# gan_buck.net
KiCad netlist of a schematic drawn in Altium Designer
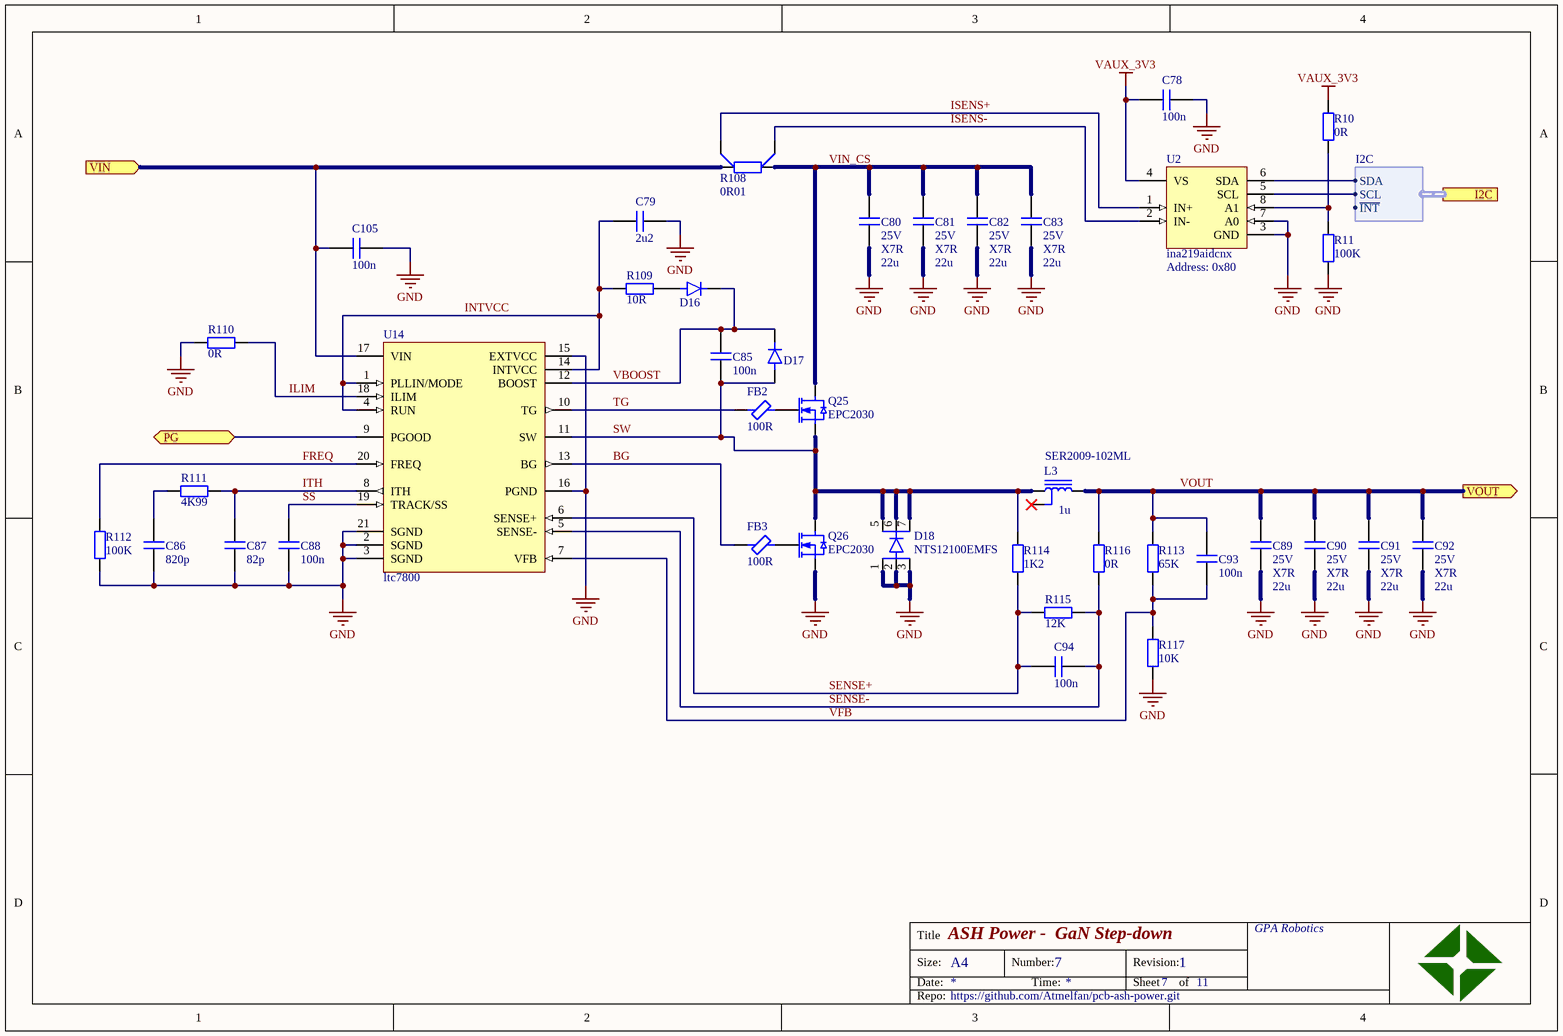
[diagram p0: gan_buck.SchDoc]

(export (version "E")
  (design (tool "Eeschema 10.0.6"))
  (components
    (comp (ref "C78")
      (value "100n")
      (footprint "CAPC1005X06N")
      (description "Capacitor")
      (fields (field (name "Comment") "cap"))
      (libsource (lib "lib_passives") (part "cap"))
    )
    (comp (ref "C79")
      (value "2u2")
      (footprint "CAPC2012X11N")
      (description "Capacitor")
      (fields (field (name "Comment") "cap"))
      (libsource (lib "lib_passives") (part "cap"))
    )
    (comp (ref "C80")
      (value "22u")
      (footprint "CAPC3225X14N")
      (description "Capacitor")
      (fields (field (name "VOLTAGE") "25V") (field (name "TYPE") "X7R") (field (name "Comment") "cap"))
      (libsource (lib "lib_passives") (part "cap"))
    )
    (comp (ref "C81")
      (value "22u")
      (footprint "CAPC3225X14N")
      (description "Capacitor")
      (fields (field (name "VOLTAGE") "25V") (field (name "TYPE") "X7R") (field (name "Comment") "cap"))
      (libsource (lib "lib_passives") (part "cap"))
    )
    (comp (ref "C82")
      (value "22u")
      (footprint "CAPC3225X14N")
      (description "Capacitor")
      (fields (field (name "VOLTAGE") "25V") (field (name "TYPE") "X7R") (field (name "Comment") "cap"))
      (libsource (lib "lib_passives") (part "cap"))
    )
    (comp (ref "C83")
      (value "22u")
      (footprint "CAPC3225X14N")
      (description "Capacitor")
      (fields (field (name "VOLTAGE") "25V") (field (name "TYPE") "X7R") (field (name "Comment") "cap"))
      (libsource (lib "lib_passives") (part "cap"))
    )
    (comp (ref "C85")
      (value "100n")
      (footprint "CAPC1608X08N")
      (description "Capacitor")
      (fields (field (name "Comment") "cap"))
      (libsource (lib "lib_passives") (part "cap"))
    )
    (comp (ref "C86")
      (value "820p")
      (footprint "CAPC1005X06N")
      (description "Capacitor")
      (fields (field (name "Comment") "cap"))
      (libsource (lib "lib_passives") (part "cap"))
    )
    (comp (ref "C87")
      (value "82p")
      (footprint "CAPC1005X06N")
      (description "Capacitor")
      (fields (field (name "Comment") "cap"))
      (libsource (lib "lib_passives") (part "cap"))
    )
    (comp (ref "C88")
      (value "100n")
      (footprint "CAPC1005X06N")
      (description "Capacitor")
      (fields (field (name "Comment") "cap"))
      (libsource (lib "lib_passives") (part "cap"))
    )
    (comp (ref "C89")
      (value "22u")
      (footprint "CAPC3225X14N")
      (description "Capacitor")
      (fields (field (name "VOLTAGE") "25V") (field (name "TYPE") "X7R") (field (name "Comment") "cap"))
      (libsource (lib "lib_passives") (part "cap"))
    )
    (comp (ref "C90")
      (value "22u")
      (footprint "CAPC3225X14N")
      (description "Capacitor")
      (fields (field (name "VOLTAGE") "25V") (field (name "TYPE") "X7R") (field (name "Comment") "cap"))
      (libsource (lib "lib_passives") (part "cap"))
    )
    (comp (ref "C91")
      (value "22u")
      (footprint "CAPC3225X14N")
      (description "Capacitor")
      (fields (field (name "VOLTAGE") "25V") (field (name "TYPE") "X7R") (field (name "Comment") "cap"))
      (libsource (lib "lib_passives") (part "cap"))
    )
    (comp (ref "C92")
      (value "22u")
      (footprint "CAPC3225X14N")
      (description "Capacitor")
      (fields (field (name "VOLTAGE") "25V") (field (name "TYPE") "X7R") (field (name "Comment") "cap"))
      (libsource (lib "lib_passives") (part "cap"))
    )
    (comp (ref "C93")
      (value "100n")
      (footprint "CAPC1005X06N")
      (description "Capacitor")
      (fields (field (name "Comment") "cap"))
      (libsource (lib "lib_passives") (part "cap"))
    )
    (comp (ref "C94")
      (value "100n")
      (footprint "CAPC1005X06N")
      (description "Capacitor")
      (fields (field (name "Comment") "cap"))
      (libsource (lib "lib_passives") (part "cap"))
    )
    (comp (ref "C105")
      (value "100n")
      (footprint "CAPC1005X06N")
      (description "Capacitor")
      (fields (field (name "Comment") "cap"))
      (libsource (lib "lib_passives") (part "cap"))
    )
    (comp (ref "D16")
      (value "DFLS2100")
      (footprint "SODFL370X100-2N_DFLS2100")
      (description "2.0A HIGH VOLTAGE SCHOTTKY BARRIER RECTIFIER")
      (libsource (lib "lib_diodesinc") (part "dfls2100"))
    )
    (comp (ref "D17")
      (value "diode")
      (footprint "CAPCP1005X06N")
      (description "Diode")
      (libsource (lib "lib_actives") (part "diode"))
    )
    (comp (ref "D18")
      (value "NTS12100EMFS")
      (footprint "SON127P620X110_HS-9N_NTS12100")
      (description "Very Low LeakageTrench-based SchottkyRectifier")
      (libsource (lib "lib_onsemi") (part "nts12100emfs"))
    )
    (comp (ref "FB2")
      (value "100R")
      (footprint "INDC1005X06N")
      (description "Inductor")
      (fields (field (name "Comment") "ferrite"))
      (libsource (lib "lib_passives") (part "ferrite"))
    )
    (comp (ref "FB3")
      (value "100R")
      (footprint "INDC1005X06N")
      (description "Inductor")
      (fields (field (name "Comment") "ferrite"))
      (libsource (lib "lib_passives") (part "ferrite"))
    )
    (comp (ref "L3")
      (value "SER2009-102ML")
      (footprint "SER20xx")
      (description "Shielded Power Inductor")
      (fields (field (name "ALTIUM_VALUE") "1u"))
      (libsource (lib "lib_coilcraft") (part "ser20xx"))
    )
    (comp (ref "Q25")
      (value "EPC2030")
      (footprint "epc2030_die")
      (description "GaN Enhancement Mode Power Transistor")
      (libsource (lib "lib_epc") (part "epc2030"))
    )
    (comp (ref "Q26")
      (value "EPC2030")
      (footprint "epc2030_die")
      (description "GaN Enhancement Mode Power Transistor")
      (libsource (lib "lib_epc") (part "epc2030"))
    )
    (comp (ref "R10")
      (value "0R")
      (footprint "RESC1005X04N")
      (description "Resistor")
      (fields (field (name "Comment") "res"))
      (libsource (lib "") (part "res_1"))
    )
    (comp (ref "R11")
      (value "100K")
      (footprint "RESC1005X04N")
      (description "Resistor")
      (fields (field (name "Comment") "res"))
      (libsource (lib "") (part "res_1"))
    )
    (comp (ref "R108")
      (value "0R01")
      (footprint "4T_RESC1632X05N")
      (description "Resistor")
      (fields (field (name "Comment") "res_4t"))
      (libsource (lib "lib_passives") (part "res_4t"))
    )
    (comp (ref "R109")
      (value "10R")
      (footprint "RESC2012X06N")
      (description "Resistor")
      (fields (field (name "Comment") "res"))
      (libsource (lib "lib_passives") (part "res"))
    )
    (comp (ref "R110")
      (value "0R")
      (footprint "RESC1005X04N")
      (description "Resistor")
      (fields (field (name "Comment") "res"))
      (libsource (lib "") (part "res_2"))
    )
    (comp (ref "R111")
      (value "4K99")
      (footprint "RESC1005X04N")
      (description "Resistor")
      (fields (field (name "Comment") "res"))
      (libsource (lib "lib_passives") (part "res"))
    )
    (comp (ref "R112")
      (value "100K")
      (footprint "RESC1005X04N")
      (description "Resistor")
      (fields (field (name "Comment") "res"))
      (libsource (lib "") (part "res_1"))
    )
    (comp (ref "R113")
      (value "65K")
      (footprint "RESC1005X04N")
      (description "Resistor")
      (fields (field (name "Comment") "res"))
      (libsource (lib "") (part "res_1"))
    )
    (comp (ref "R114")
      (value "1K2")
      (footprint "RESC1005X04N")
      (description "Resistor")
      (fields (field (name "Comment") "res"))
      (libsource (lib "") (part "res_1"))
    )
    (comp (ref "R115")
      (value "12K")
      (footprint "RESC1005X04N")
      (description "Resistor")
      (fields (field (name "Comment") "res"))
      (libsource (lib "") (part "res_2"))
    )
    (comp (ref "R116")
      (value "0R")
      (footprint "RESC1005X04N")
      (description "Resistor")
      (fields (field (name "Comment") "res"))
      (libsource (lib "") (part "res_1"))
    )
    (comp (ref "R117")
      (value "10K")
      (footprint "RESC1005X04N")
      (description "Resistor")
      (fields (field (name "Comment") "res"))
      (libsource (lib "") (part "res_1"))
    )
    (comp (ref "U2")
      (value "ina219aidcnx")
      (footprint "TSOP65P280X145-8N")
      (description "INA219 Zero-Drift, Bidirectional Current/Power Monitor With I2C Interface")
      (fields (field (name "ADDRESS") "0x80"))
      (libsource (lib "lib_ti") (part "ina219aidcnx"))
    )
    (comp (ref "U14")
      (value "ltc7800")
      (footprint "QFN50P300X400X80_HS-21N_LTC7800")
      (description "Low IQ, 60V, High Frequency Synchronous Step-Down Controller")
      (libsource (lib "lib_lineartech") (part "ltc7800"))
    )
  )
  (nets
    (net (code "2") (name "/BG") (class "Default")
      (node (ref "FB3") (pin "1") (pinfunction "1_1") (pintype "passive"))
      (node (ref "U14") (pin "13") (pinfunction "BG_13") (pintype "output"))
    )
    (net (code "3") (name "/FREQ") (class "Default")
      (node (ref "R112") (pin "2") (pinfunction "2_2") (pintype "passive"))
      (node (ref "U14") (pin "20") (pinfunction "FREQ_20") (pintype "input"))
    )
    (net (code "4") (name "/ILIM") (class "Default")
      (node (ref "R110") (pin "1") (pinfunction "1_1") (pintype "passive"))
      (node (ref "U14") (pin "18") (pinfunction "ILIM_18") (pintype "input"))
    )
    (net (code "5") (name "/INTVCC") (class "Default")
      (node (ref "C79") (pin "1") (pinfunction "1_1") (pintype "passive"))
      (node (ref "R109") (pin "1") (pinfunction "1_1") (pintype "passive"))
      (node (ref "U14") (pin "1") (pinfunction "PLLIN/MODE_1") (pintype "input"))
      (node (ref "U14") (pin "14") (pinfunction "INTVCC_14") (pintype "power_in"))
      (node (ref "U14") (pin "4") (pinfunction "RUN_4") (pintype "input"))
    )
    (net (code "6") (name "/ISENS+") (class "Default")
      (node (ref "R108") (pin "4") (pinfunction "4_4") (pintype "passive"))
      (node (ref "U2") (pin "1") (pinfunction "IN+_1") (pintype "input"))
    )
    (net (code "7") (name "/ISENS-") (class "Default")
      (node (ref "R108") (pin "3") (pinfunction "3_3") (pintype "passive"))
      (node (ref "U2") (pin "2") (pinfunction "IN-_2") (pintype "input"))
    )
    (net (code "8") (name "/ITH") (class "Default")
      (node (ref "C87") (pin "2") (pinfunction "2_2") (pintype "passive"))
      (node (ref "R111") (pin "2") (pinfunction "2_2") (pintype "passive"))
      (node (ref "U14") (pin "8") (pinfunction "ITH_8") (pintype "output"))
    )
    (net (code "9") (name "/PG") (class "Default")
      (node (ref "U14") (pin "9") (pinfunction "PGOOD_9") (pintype "open_collector"))
    )
    (net (code "10") (name "/SCL") (class "Default")
      (node (ref "U2") (pin "5") (pinfunction "SCL_5") (pintype "open_collector"))
    )
    (net (code "11") (name "/SDA") (class "Default")
      (node (ref "U2") (pin "6") (pinfunction "SDA_6") (pintype "open_collector"))
    )
    (net (code "12") (name "/SENSE+") (class "Default")
      (node (ref "C94") (pin "1") (pinfunction "1_1") (pintype "passive"))
      (node (ref "R114") (pin "1") (pinfunction "1_1") (pintype "passive"))
      (node (ref "R115") (pin "2") (pinfunction "2_2") (pintype "passive"))
      (node (ref "U14") (pin "6") (pinfunction "SENSE+_6") (pintype "input"))
    )
    (net (code "13") (name "/SENSE-") (class "Default")
      (node (ref "C94") (pin "2") (pinfunction "2_2") (pintype "passive"))
      (node (ref "R115") (pin "1") (pinfunction "1_1") (pintype "passive"))
      (node (ref "R116") (pin "1") (pinfunction "1_1") (pintype "passive"))
      (node (ref "U14") (pin "5") (pinfunction "SENSE-_5") (pintype "input"))
    )
    (net (code "14") (name "/SS") (class "Default")
      (node (ref "C88") (pin "2") (pinfunction "2_2") (pintype "passive"))
      (node (ref "U14") (pin "19") (pinfunction "TRACK/SS_19") (pintype "input"))
    )
    (net (code "15") (name "/SW") (class "Default")
      (node (ref "C85") (pin "1") (pinfunction "1_1") (pintype "passive"))
      (node (ref "D17") (pin "A") (pinfunction "A_A") (pintype "passive"))
      (node (ref "D18") (pin "5") (pinfunction "5_5") (pintype "passive"))
      (node (ref "D18") (pin "6") (pinfunction "6_6") (pintype "passive"))
      (node (ref "D18") (pin "7") (pinfunction "7_7") (pintype "passive"))
      (node (ref "L3") (pin "2") (pinfunction "2_2") (pintype "passive"))
      (node (ref "Q25") (pin "S") (pinfunction "S_S") (pintype "passive"))
      (node (ref "Q26") (pin "D") (pinfunction "D_D") (pintype "passive"))
      (node (ref "R114") (pin "2") (pinfunction "2_2") (pintype "passive"))
      (node (ref "U14") (pin "11") (pinfunction "SW_11") (pintype "passive"))
    )
    (net (code "16") (name "/TG") (class "Default")
      (node (ref "FB2") (pin "1") (pinfunction "1_1") (pintype "passive"))
      (node (ref "U14") (pin "10") (pinfunction "TG_10") (pintype "output"))
    )
    (net (code "17") (name "/VBOOST") (class "Default")
      (node (ref "C85") (pin "2") (pinfunction "2_2") (pintype "passive"))
      (node (ref "D16") (pin "C") (pinfunction "C_C") (pintype "passive"))
      (node (ref "D17") (pin "C") (pinfunction "C_C") (pintype "passive"))
      (node (ref "U14") (pin "12") (pinfunction "BOOST_12") (pintype "passive"))
    )
    (net (code "18") (name "/VFB") (class "Default")
      (node (ref "C93") (pin "1") (pinfunction "1_1") (pintype "passive"))
      (node (ref "R113") (pin "1") (pinfunction "1_1") (pintype "passive"))
      (node (ref "R117") (pin "2") (pinfunction "2_2") (pintype "passive"))
      (node (ref "U14") (pin "7") (pinfunction "VFB_7") (pintype "input"))
    )
    (net (code "19") (name "/VIN") (class "Default")
      (node (ref "C105") (pin "1") (pinfunction "1_1") (pintype "passive"))
      (node (ref "R108") (pin "2") (pinfunction "2_2") (pintype "passive"))
      (node (ref "U14") (pin "17") (pinfunction "VIN_17") (pintype "power_in"))
    )
    (net (code "20") (name "/VIN_CS") (class "Default")
      (node (ref "C80") (pin "1") (pinfunction "1_1") (pintype "passive"))
      (node (ref "C81") (pin "1") (pinfunction "1_1") (pintype "passive"))
      (node (ref "C82") (pin "1") (pinfunction "1_1") (pintype "passive"))
      (node (ref "C83") (pin "1") (pinfunction "1_1") (pintype "passive"))
      (node (ref "Q25") (pin "D") (pinfunction "D_D") (pintype "passive"))
      (node (ref "R108") (pin "1") (pinfunction "1_1") (pintype "passive"))
    )
    (net (code "21") (name "/VOUT") (class "Default")
      (node (ref "C89") (pin "1") (pinfunction "1_1") (pintype "passive"))
      (node (ref "C90") (pin "1") (pinfunction "1_1") (pintype "passive"))
      (node (ref "C91") (pin "1") (pinfunction "1_1") (pintype "passive"))
      (node (ref "C92") (pin "1") (pinfunction "1_1") (pintype "passive"))
      (node (ref "C93") (pin "2") (pinfunction "2_2") (pintype "passive"))
      (node (ref "L3") (pin "1") (pinfunction "1_1") (pintype "passive"))
      (node (ref "R113") (pin "2") (pinfunction "2_2") (pintype "passive"))
      (node (ref "R116") (pin "2") (pinfunction "2_2") (pintype "passive"))
    )
    (net (code "23") (name "GND") (class "Default")
      (node (ref "C105") (pin "2") (pinfunction "2_2") (pintype "passive"))
      (node (ref "C78") (pin "1") (pinfunction "1_1") (pintype "passive"))
      (node (ref "C79") (pin "2") (pinfunction "2_2") (pintype "passive"))
      (node (ref "C80") (pin "2") (pinfunction "2_2") (pintype "passive"))
      (node (ref "C81") (pin "2") (pinfunction "2_2") (pintype "passive"))
      (node (ref "C82") (pin "2") (pinfunction "2_2") (pintype "passive"))
      (node (ref "C83") (pin "2") (pinfunction "2_2") (pintype "passive"))
      (node (ref "C86") (pin "1") (pinfunction "1_1") (pintype "passive"))
      (node (ref "C87") (pin "1") (pinfunction "1_1") (pintype "passive"))
      (node (ref "C88") (pin "1") (pinfunction "1_1") (pintype "passive"))
      (node (ref "C89") (pin "2") (pinfunction "2_2") (pintype "passive"))
      (node (ref "C90") (pin "2") (pinfunction "2_2") (pintype "passive"))
      (node (ref "C91") (pin "2") (pinfunction "2_2") (pintype "passive"))
      (node (ref "C92") (pin "2") (pinfunction "2_2") (pintype "passive"))
      (node (ref "D18") (pin "1") (pinfunction "1_1") (pintype "passive"))
      (node (ref "D18") (pin "2") (pinfunction "2_2") (pintype "passive"))
      (node (ref "D18") (pin "3") (pinfunction "3_3") (pintype "passive"))
      (node (ref "Q26") (pin "S") (pinfunction "S_S") (pintype "passive"))
      (node (ref "R11") (pin "1") (pinfunction "1_1") (pintype "passive"))
      (node (ref "R110") (pin "2") (pinfunction "2_2") (pintype "passive"))
      (node (ref "R112") (pin "1") (pinfunction "1_1") (pintype "passive"))
      (node (ref "R117") (pin "1") (pinfunction "1_1") (pintype "passive"))
      (node (ref "U14") (pin "15") (pinfunction "EXTVCC_15") (pintype "power_in"))
      (node (ref "U14") (pin "16") (pinfunction "PGND_16") (pintype "power_in"))
      (node (ref "U14") (pin "2") (pinfunction "SGND_2") (pintype "power_in"))
      (node (ref "U14") (pin "21") (pinfunction "SGND_21") (pintype "power_in"))
      (node (ref "U14") (pin "3") (pinfunction "SGND_3") (pintype "power_in"))
      (node (ref "U2") (pin "3") (pinfunction "GND_3") (pintype "power_in"))
      (node (ref "U2") (pin "7") (pinfunction "A0_7") (pintype "input"))
    )
    (net (code "24") (name "Net-(C86-Pad2)") (class "Default")
      (node (ref "C86") (pin "2") (pinfunction "2_2") (pintype "passive"))
      (node (ref "R111") (pin "1") (pinfunction "1_1") (pintype "passive"))
    )
    (net (code "25") (name "Net-(D16-PadA)") (class "Default")
      (node (ref "D16") (pin "A") (pinfunction "A_A") (pintype "passive"))
      (node (ref "R109") (pin "2") (pinfunction "2_2") (pintype "passive"))
    )
    (net (code "26") (name "Net-(FB2-Pad2)") (class "Default")
      (node (ref "FB2") (pin "2") (pinfunction "2_2") (pintype "passive"))
      (node (ref "Q25") (pin "G") (pinfunction "G_G") (pintype "passive"))
    )
    (net (code "27") (name "Net-(FB3-Pad2)") (class "Default")
      (node (ref "FB3") (pin "2") (pinfunction "2_2") (pintype "passive"))
      (node (ref "Q26") (pin "G") (pinfunction "G_G") (pintype "passive"))
    )
    (net (code "28") (name "Net-(U2-A1)") (class "Default")
      (node (ref "R10") (pin "1") (pinfunction "1_1") (pintype "passive"))
      (node (ref "R11") (pin "2") (pinfunction "2_2") (pintype "passive"))
      (node (ref "U2") (pin "8") (pinfunction "A1_8") (pintype "input"))
    )
    (net (code "29") (name "VAUX_3V3") (class "Default")
      (node (ref "C78") (pin "2") (pinfunction "2_2") (pintype "passive"))
      (node (ref "R10") (pin "2") (pinfunction "2_2") (pintype "passive"))
      (node (ref "U2") (pin "4") (pinfunction "VS_4") (pintype "power_in"))
    )
    (net (code "30") (name "unconnected-(L3-Pad3)") (class "Default")
      (node (ref "L3") (pin "3") (pinfunction "3_3") (pintype "passive+no_connect"))
    )
  )
)
